# iBizi-V1A.net
KiCad netlist of a schematic drawn in EAGLE
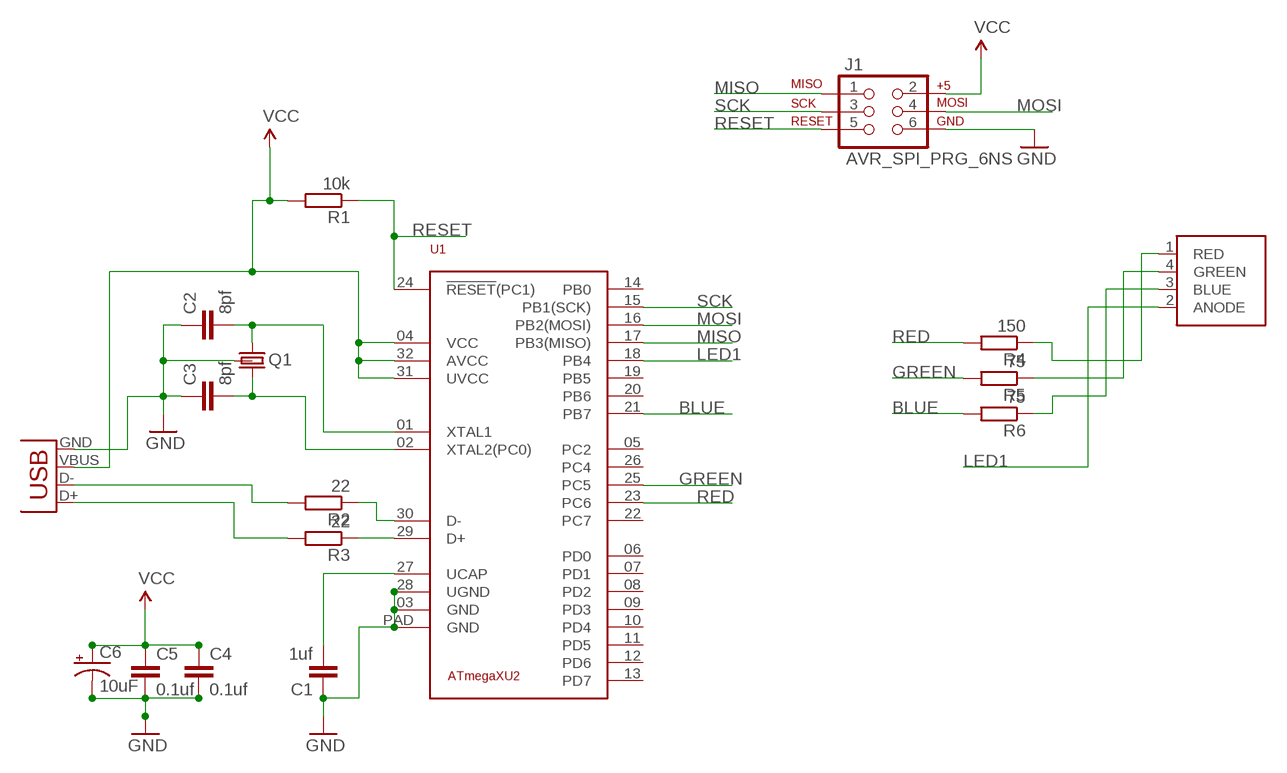
[diagram p0: schematic, sheet 1]

(export (version "E")
  (design (tool "Eeschema 10.0.6"))
  (components
    (comp (ref "C1")
      (value "1uf")
      (footprint "eagle-import:C0402")
      (libsource (lib "eagle-import") (part "C-EUC0402"))
    )
    (comp (ref "C2")
      (value "8pf")
      (footprint "eagle-import:C0402")
      (libsource (lib "eagle-import") (part "C-EUC0402"))
    )
    (comp (ref "C3")
      (value "8pf")
      (footprint "eagle-import:C0402")
      (libsource (lib "eagle-import") (part "C-EUC0402"))
    )
    (comp (ref "C4")
      (value "0.1uf")
      (footprint "eagle-import:C0402")
      (libsource (lib "eagle-import") (part "C-EUC0402"))
    )
    (comp (ref "C5")
      (value "0.1uf")
      (footprint "eagle-import:C0402")
      (libsource (lib "eagle-import") (part "C-EUC0402"))
    )
    (comp (ref "C6")
      (value "10uF")
      (footprint "eagle-import:EIA3216")
      (libsource (lib "eagle-import") (part "10UF-16V-10%(TANT)"))
    )
    (comp (ref "J1")
      (value "AVR_SPI_PRG_6NS")
      (footprint "eagle-import:2X3-NS")
      (libsource (lib "eagle-import") (part "AVR_SPI_PRG_6NS"))
    )
    (comp (ref "LED1")
      (value "RGB-LED-CLV1A-FKB")
      (footprint "eagle-import:PLCC4")
      (libsource (lib "eagle-import") (part "RGB-LED-CLV1A-FKB"))
    )
    (comp (ref "Q1")
      (value "CRYSTAL-EPSON-TSX3225-3.2X2.5")
      (footprint "eagle-import:CRYSTAL-SMD-3.2X2.5")
      (libsource (lib "eagle-import") (part "CRYSTAL-EPSON-TSX3225-3.2X2.5"))
    )
    (comp (ref "R1")
      (value "10k")
      (footprint "eagle-import:R0402")
      (libsource (lib "eagle-import") (part "R-EU_R0402"))
    )
    (comp (ref "R2")
      (value "22")
      (footprint "eagle-import:R0402")
      (libsource (lib "eagle-import") (part "R-EU_R0402"))
    )
    (comp (ref "R3")
      (value "22")
      (footprint "eagle-import:R0402")
      (libsource (lib "eagle-import") (part "R-EU_R0402"))
    )
    (comp (ref "R4")
      (value "150")
      (footprint "eagle-import:R0402")
      (libsource (lib "eagle-import") (part "R-EU_R0402"))
    )
    (comp (ref "R5")
      (value "75")
      (footprint "eagle-import:R0402")
      (libsource (lib "eagle-import") (part "R-EU_R0402"))
    )
    (comp (ref "R6")
      (value "75")
      (footprint "eagle-import:R0402")
      (libsource (lib "eagle-import") (part "R-EU_R0402"))
    )
    (comp (ref "U1")
      (value "ATMEGAXU2")
      (footprint "eagle-import:QFN32")
      (libsource (lib "eagle-import") (part "ATMEGAXU2"))
    )
    (comp (ref "USB")
      (value "USBSMD")
      (footprint "eagle-import:USB-MINIB")
      (libsource (lib "eagle-import") (part "USBSMD"))
    )
  )
  (nets
    (net (code "1") (name "/BLUE") (class "Default")
      (node (ref "R6") (pin "2") (pinfunction "2_2") (pintype "passive"))
      (node (ref "U1") (pin "21") (pinfunction "PB7_21") (pintype "bidirectional"))
    )
    (net (code "2") (name "/GREEN") (class "Default")
      (node (ref "R5") (pin "2") (pinfunction "2_2") (pintype "passive"))
      (node (ref "U1") (pin "25") (pinfunction "PC5_25") (pintype "bidirectional"))
    )
    (net (code "3") (name "/LED1") (class "Default")
      (node (ref "LED1") (pin "2") (pinfunction "ANODE_2") (pintype "bidirectional"))
      (node (ref "U1") (pin "18") (pinfunction "PB4_18") (pintype "bidirectional"))
    )
    (net (code "4") (name "/MISO") (class "Default")
      (node (ref "J1") (pin "1") (pinfunction "1_1") (pintype "passive"))
      (node (ref "U1") (pin "17") (pinfunction "PB3(MISO)_17") (pintype "bidirectional"))
    )
    (net (code "5") (name "/MOSI") (class "Default")
      (node (ref "J1") (pin "4") (pinfunction "4_4") (pintype "passive"))
      (node (ref "U1") (pin "16") (pinfunction "PB2(MOSI)_16") (pintype "bidirectional"))
    )
    (net (code "6") (name "/RED") (class "Default")
      (node (ref "R4") (pin "2") (pinfunction "2_2") (pintype "passive"))
      (node (ref "U1") (pin "23") (pinfunction "PC6_23") (pintype "bidirectional"))
    )
    (net (code "7") (name "/RESET") (class "Default")
      (node (ref "J1") (pin "5") (pinfunction "5_5") (pintype "passive"))
      (node (ref "R1") (pin "1") (pinfunction "1_1") (pintype "passive"))
      (node (ref "U1") (pin "24") (pinfunction "~{RESET}(PC1)_24") (pintype "bidirectional"))
    )
    (net (code "8") (name "/SCK") (class "Default")
      (node (ref "J1") (pin "3") (pinfunction "3_3") (pintype "passive"))
      (node (ref "U1") (pin "15") (pinfunction "PB1(SCK)_15") (pintype "bidirectional"))
    )
    (net (code "9") (name "GND") (class "Default")
      (node (ref "C1") (pin "1") (pinfunction "1_1") (pintype "passive"))
      (node (ref "C2") (pin "1") (pinfunction "1_1") (pintype "passive"))
      (node (ref "C3") (pin "1") (pinfunction "1_1") (pintype "passive"))
      (node (ref "C4") (pin "2") (pinfunction "2_2") (pintype "passive"))
      (node (ref "C5") (pin "2") (pinfunction "2_2") (pintype "passive"))
      (node (ref "C6") (pin "C") (pinfunction "-_C") (pintype "passive"))
      (node (ref "J1") (pin "6") (pinfunction "6_6") (pintype "passive"))
      (node (ref "Q1") (pin "2") (pinfunction "GND_2") (pintype "power_in"))
      (node (ref "Q1") (pin "4") (pinfunction "GND_4") (pintype "power_in"))
      (node (ref "U1") (pin "03") (pinfunction "GND_03") (pintype "power_in"))
      (node (ref "U1") (pin "28") (pinfunction "UGND_28") (pintype "power_in"))
      (node (ref "U1") (pin "PAD") (pinfunction "GND_PAD") (pintype "power_in"))
      (node (ref "USB") (pin "GND") (pinfunction "GND_GND") (pintype "bidirectional"))
    )
    (net (code "10") (name "Net-(LED1-BLUE)") (class "Default")
      (node (ref "LED1") (pin "3") (pinfunction "BLUE_3") (pintype "bidirectional"))
      (node (ref "R6") (pin "1") (pinfunction "1_1") (pintype "passive"))
    )
    (net (code "11") (name "Net-(LED1-GREEN)") (class "Default")
      (node (ref "LED1") (pin "4") (pinfunction "GREEN_4") (pintype "bidirectional"))
      (node (ref "R5") (pin "1") (pinfunction "1_1") (pintype "passive"))
    )
    (net (code "12") (name "Net-(LED1-RED)") (class "Default")
      (node (ref "LED1") (pin "1") (pinfunction "RED_1") (pintype "bidirectional"))
      (node (ref "R4") (pin "1") (pinfunction "1_1") (pintype "passive"))
    )
    (net (code "13") (name "Net-(Q1-2)") (class "Default")
      (node (ref "C3") (pin "2") (pinfunction "2_2") (pintype "passive"))
      (node (ref "Q1") (pin "3") (pinfunction "2_3") (pintype "passive"))
      (node (ref "U1") (pin "02") (pinfunction "XTAL2(PC0)_02") (pintype "bidirectional"))
    )
    (net (code "14") (name "Net-(R2-Pad2)") (class "Default")
      (node (ref "R2") (pin "2") (pinfunction "2_2") (pintype "passive"))
      (node (ref "USB") (pin "D-") (pinfunction "D-_D-") (pintype "bidirectional"))
    )
    (net (code "15") (name "Net-(R3-Pad2)") (class "Default")
      (node (ref "R3") (pin "2") (pinfunction "2_2") (pintype "passive"))
      (node (ref "USB") (pin "D+") (pinfunction "D+_D+") (pintype "bidirectional"))
    )
    (net (code "16") (name "Net-(U1-D+)") (class "Default")
      (node (ref "R3") (pin "1") (pinfunction "1_1") (pintype "passive"))
      (node (ref "U1") (pin "29") (pinfunction "D+_29") (pintype "bidirectional"))
    )
    (net (code "17") (name "Net-(U1-D-)") (class "Default")
      (node (ref "R2") (pin "1") (pinfunction "1_1") (pintype "passive"))
      (node (ref "U1") (pin "30") (pinfunction "D-_30") (pintype "bidirectional"))
    )
    (net (code "18") (name "Net-(U1-UCAP)") (class "Default")
      (node (ref "C1") (pin "2") (pinfunction "2_2") (pintype "passive"))
      (node (ref "U1") (pin "27") (pinfunction "UCAP_27") (pintype "bidirectional"))
    )
    (net (code "19") (name "Net-(U1-XTAL1)") (class "Default")
      (node (ref "C2") (pin "2") (pinfunction "2_2") (pintype "passive"))
      (node (ref "Q1") (pin "1") (pinfunction "1_1") (pintype "passive"))
      (node (ref "U1") (pin "01") (pinfunction "XTAL1_01") (pintype "bidirectional"))
    )
    (net (code "20") (name "VCC") (class "Default")
      (node (ref "C4") (pin "1") (pinfunction "1_1") (pintype "passive"))
      (node (ref "C5") (pin "1") (pinfunction "1_1") (pintype "passive"))
      (node (ref "C6") (pin "A") (pinfunction "+_A") (pintype "passive"))
      (node (ref "J1") (pin "2") (pinfunction "2_2") (pintype "passive"))
      (node (ref "R1") (pin "2") (pinfunction "2_2") (pintype "passive"))
      (node (ref "U1") (pin "04") (pinfunction "VCC_04") (pintype "power_in"))
      (node (ref "U1") (pin "31") (pinfunction "UVCC_31") (pintype "power_in"))
      (node (ref "U1") (pin "32") (pinfunction "AVCC_32") (pintype "power_in"))
      (node (ref "USB") (pin "VBUS") (pinfunction "VBUS_VBUS") (pintype "bidirectional"))
    )
    (net (code "21") (name "unconnected-(U1-PB0-Pad14)") (class "Default")
      (node (ref "U1") (pin "14") (pinfunction "PB0_14") (pintype "bidirectional"))
    )
    (net (code "22") (name "unconnected-(U1-PB5-Pad19)") (class "Default")
      (node (ref "U1") (pin "19") (pinfunction "PB5_19") (pintype "bidirectional"))
    )
    (net (code "23") (name "unconnected-(U1-PB6-Pad20)") (class "Default")
      (node (ref "U1") (pin "20") (pinfunction "PB6_20") (pintype "bidirectional"))
    )
    (net (code "24") (name "unconnected-(U1-PC2-Pad05)") (class "Default")
      (node (ref "U1") (pin "05") (pinfunction "PC2_05") (pintype "bidirectional"))
    )
    (net (code "25") (name "unconnected-(U1-PC4-Pad26)") (class "Default")
      (node (ref "U1") (pin "26") (pinfunction "PC4_26") (pintype "bidirectional"))
    )
    (net (code "26") (name "unconnected-(U1-PC7-Pad22)") (class "Default")
      (node (ref "U1") (pin "22") (pinfunction "PC7_22") (pintype "bidirectional"))
    )
    (net (code "27") (name "unconnected-(U1-PD0-Pad06)") (class "Default")
      (node (ref "U1") (pin "06") (pinfunction "PD0_06") (pintype "bidirectional"))
    )
    (net (code "28") (name "unconnected-(U1-PD1-Pad07)") (class "Default")
      (node (ref "U1") (pin "07") (pinfunction "PD1_07") (pintype "bidirectional"))
    )
    (net (code "29") (name "unconnected-(U1-PD2-Pad08)") (class "Default")
      (node (ref "U1") (pin "08") (pinfunction "PD2_08") (pintype "bidirectional"))
    )
    (net (code "30") (name "unconnected-(U1-PD3-Pad09)") (class "Default")
      (node (ref "U1") (pin "09") (pinfunction "PD3_09") (pintype "bidirectional"))
    )
    (net (code "31") (name "unconnected-(U1-PD4-Pad10)") (class "Default")
      (node (ref "U1") (pin "10") (pinfunction "PD4_10") (pintype "bidirectional"))
    )
    (net (code "32") (name "unconnected-(U1-PD5-Pad11)") (class "Default")
      (node (ref "U1") (pin "11") (pinfunction "PD5_11") (pintype "bidirectional"))
    )
    (net (code "33") (name "unconnected-(U1-PD6-Pad12)") (class "Default")
      (node (ref "U1") (pin "12") (pinfunction "PD6_12") (pintype "bidirectional"))
    )
    (net (code "34") (name "unconnected-(U1-PD7-Pad13)") (class "Default")
      (node (ref "U1") (pin "13") (pinfunction "PD7_13") (pintype "bidirectional"))
    )
  )
)
